# Inputs.net
KiCad netlist of a schematic drawn in Altium Designer
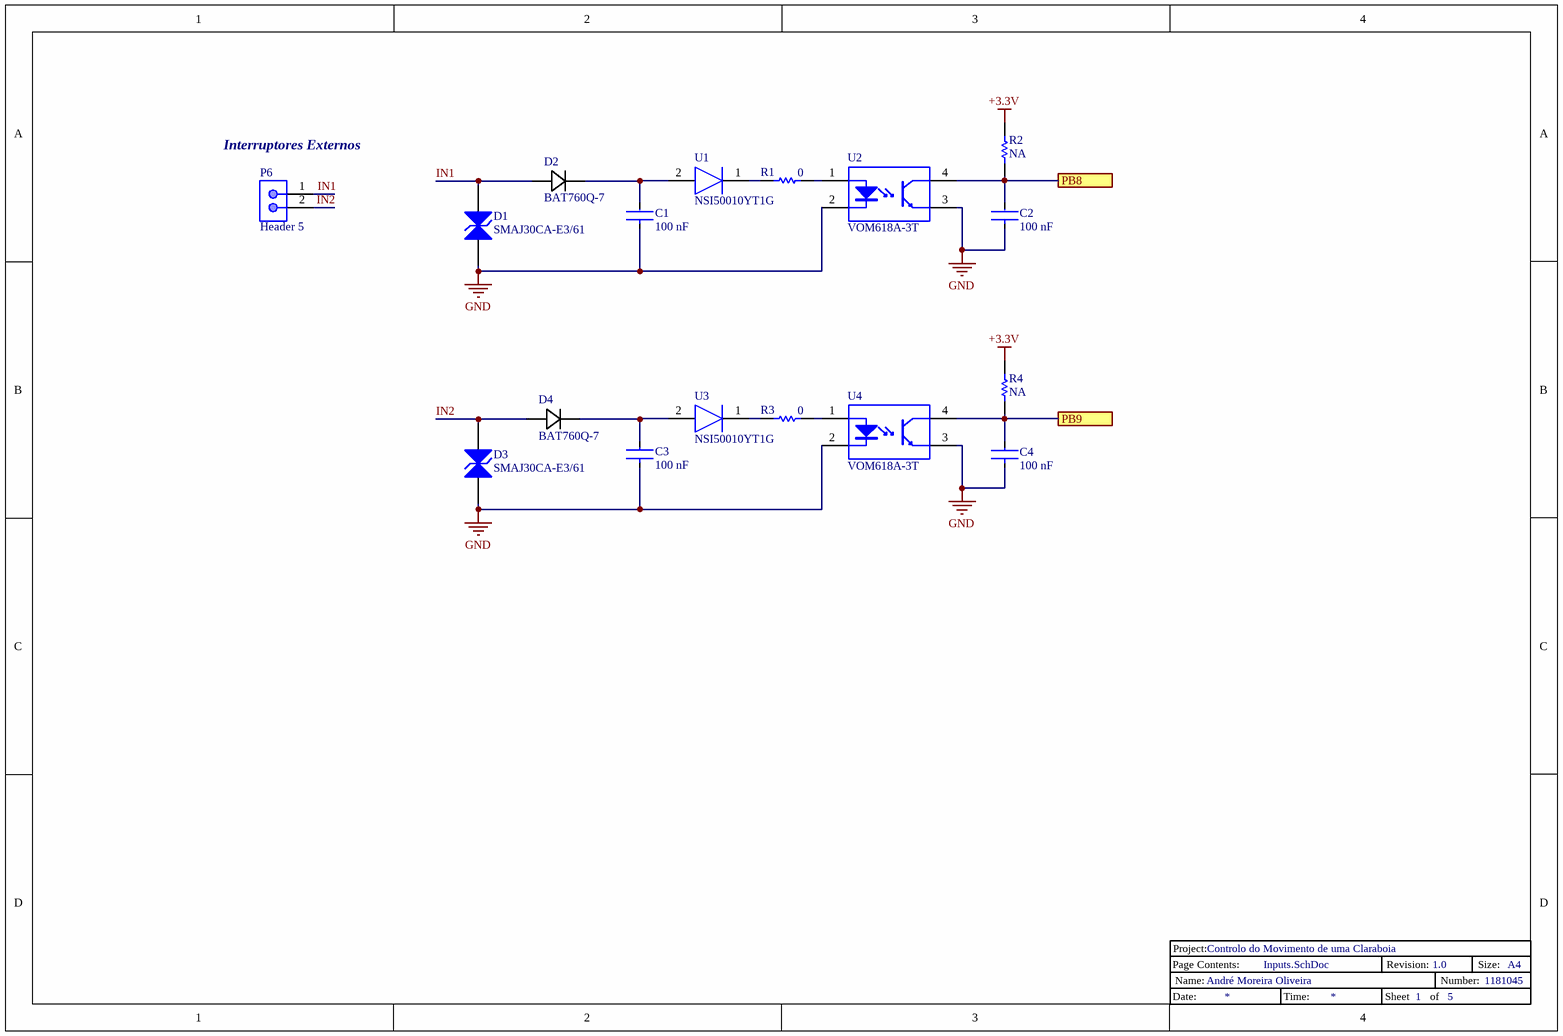
[diagram p0: Inputs.SchDoc]

(export (version "E")
  (design (tool "Eeschema 10.0.6"))
  (components
    (comp (ref "C1")
      (value "100 nF")
      (footprint "FP-CC0603-DA-MFG")
      (description "CAP CER 0.1UF 50V X7R 0603")
      (fields (field (name "MANUFACTURER") "YAGEO") (field (name "VOLTAGE") "50 V"))
      (libsource (lib "Altium Content Vault") (part "11868f565c42a9108669ba33697ecf6"))
    )
    (comp (ref "C2")
      (value "100 nF")
      (footprint "FP-CC0603-DA-MFG")
      (description "CAP CER 0.1UF 50V X7R 0603")
      (fields (field (name "MANUFACTURER") "YAGEO") (field (name "VOLTAGE") "50 V"))
      (libsource (lib "Altium Content Vault") (part "11868f565c42a9108669ba33697ecf6"))
    )
    (comp (ref "C3")
      (value "100 nF")
      (footprint "FP-CC0603-DA-MFG")
      (description "CAP CER 0.1UF 50V X7R 0603")
      (fields (field (name "MANUFACTURER") "YAGEO") (field (name "VOLTAGE") "50 V"))
      (libsource (lib "Altium Content Vault") (part "11868f565c42a9108669ba33697ecf6"))
    )
    (comp (ref "C4")
      (value "100 nF")
      (footprint "FP-CC0603-DA-MFG")
      (description "CAP CER 0.1UF 50V X7R 0603")
      (fields (field (name "MANUFACTURER") "YAGEO") (field (name "VOLTAGE") "50 V"))
      (libsource (lib "Altium Content Vault") (part "11868f565c42a9108669ba33697ecf6"))
    )
    (comp (ref "D1")
      (value "SMAJ30CA-E3/61")
      (footprint "VISH-DO-214AC-2_L")
      (fields (field (name "MANUFACTURER") "Vishay Semiconductor"))
      (libsource (lib "Altium Content Vault") (part "VISH-A1A2-2"))
    )
    (comp (ref "D2")
      (value "BAT760Q-7")
      (footprint "DIODE_SOD-323_1P7X1P3_DIO-L")
      (description "No Description Available")
      (fields (field (name "COPYRIGHT") "Copyright (C) 2018 Accelerated Designs. All rights reserved"))
      (libsource (lib "BAT760Q-7") (part "BAT760Q-7"))
    )
    (comp (ref "D3")
      (value "SMAJ30CA-E3/61")
      (footprint "VISH-DO-214AC-2_L")
      (fields (field (name "MANUFACTURER") "Vishay Semiconductor"))
      (libsource (lib "Altium Content Vault") (part "VISH-A1A2-2"))
    )
    (comp (ref "D4")
      (value "BAT760Q-7")
      (footprint "DIODE_SOD-323_1P7X1P3_DIO-L")
      (description "No Description Available")
      (fields (field (name "COPYRIGHT") "Copyright (C) 2018 Accelerated Designs. All rights reserved"))
      (libsource (lib "BAT760Q-7") (part "BAT760Q-7"))
    )
    (comp (ref "P6")
      (value "Header 5")
      (footprint "MOLX-22-27-2021_V")
      (fields (field (name "MANUFACTURER") "Molex") (field (name "PARTNUMBER") "0022272021"))
      (libsource (lib "Altium Content Vault") (part "CN-1P-M-R2"))
    )
    (comp (ref "R1")
      (value "0")
      (footprint "RESC1608X55X25ML10T15")
      (description "Chip Resistor, 0 Ohm, +/- 5%, 0.1 W, -55 to 155 degC, 0603 (1608 Metric), RoHS, Tape and Reel")
      (fields (field (name "TOLERANCE") "5%") (field (name "MANUFACTURER") "Yageo"))
      (libsource (lib "Altium Content Vault") (part "RES-2"))
    )
    (comp (ref "R2")
      (value "NA")
      (footprint "RESC1608X55X25ML10T15")
      (description "Chip Resistor, 0 Ohm, +/- 5%, 0.1 W, -55 to 155 degC, 0603 (1608 Metric), RoHS, Tape and Reel")
      (fields (field (name "TOLERANCE") "5%") (field (name "MANUFACTURER") "Yageo"))
      (libsource (lib "Altium Content Vault") (part "RES-2"))
    )
    (comp (ref "R3")
      (value "0")
      (footprint "RESC1608X55X25ML10T15")
      (description "Chip Resistor, 0 Ohm, +/- 5%, 0.1 W, -55 to 155 degC, 0603 (1608 Metric), RoHS, Tape and Reel")
      (fields (field (name "TOLERANCE") "5%") (field (name "MANUFACTURER") "Yageo"))
      (libsource (lib "Altium Content Vault") (part "RES-2"))
    )
    (comp (ref "R4")
      (value "NA")
      (footprint "RESC1608X55X25ML10T15")
      (description "Chip Resistor, 0 Ohm, +/- 5%, 0.1 W, -55 to 155 degC, 0603 (1608 Metric), RoHS, Tape and Reel")
      (fields (field (name "TOLERANCE") "5%") (field (name "MANUFACTURER") "Yageo"))
      (libsource (lib "Altium Content Vault") (part "RES-2"))
    )
    (comp (ref "Title_Block_1") (value "Title_Block") (libsource (lib "Title_Block") (part "Title_Block")))
    (comp (ref "U1")
      (value "NSI50010YT1G")
      (footprint "SamacSys:SOD3716X135N")
      (description "Diode")
      (fields (field (name "MOUSER PART NUMBER") "863-NSI50010YT1G"))
      (libsource (lib "*") (part "NSI50010YT1G"))
    )
    (comp (ref "U2")
      (value "VOM618A-3T")
      (footprint "VISH-SOP-4_V")
      (fields (field (name "MANUFACTURER") "Vishay"))
      (libsource (lib "Altium Content Vault") (part "OPTO-AKEC-4"))
    )
    (comp (ref "U3")
      (value "NSI50010YT1G")
      (footprint "SamacSys:SOD3716X135N")
      (description "Diode")
      (fields (field (name "MOUSER PART NUMBER") "863-NSI50010YT1G"))
      (libsource (lib "*") (part "NSI50010YT1G"))
    )
    (comp (ref "U4")
      (value "VOM618A-3T")
      (footprint "VISH-SOP-4_V")
      (fields (field (name "MANUFACTURER") "Vishay"))
      (libsource (lib "Altium Content Vault") (part "OPTO-AKEC-4"))
    )
  )
  (nets
    (net (code "1") (name "+3.3V") (class "Default")
      (node (ref "R2") (pin "2") (pinfunction "2_2") (pintype "passive"))
      (node (ref "R4") (pin "2") (pinfunction "2_2") (pintype "passive"))
    )
    (net (code "2") (name "/IN1") (class "Default")
      (node (ref "D1") (pin "2") (pinfunction "A2_2") (pintype "passive"))
      (node (ref "D2") (pin "2") (pinfunction "2_2") (pintype "passive"))
      (node (ref "P6") (pin "1") (pinfunction "1_1") (pintype "passive"))
    )
    (net (code "3") (name "/IN2") (class "Default")
      (node (ref "D3") (pin "2") (pinfunction "A2_2") (pintype "passive"))
      (node (ref "D4") (pin "2") (pinfunction "2_2") (pintype "passive"))
      (node (ref "P6") (pin "2") (pinfunction "2_2") (pintype "passive"))
    )
    (net (code "4") (name "/PB8") (class "Default")
      (node (ref "C2") (pin "2") (pinfunction "2_2") (pintype "passive"))
      (node (ref "R2") (pin "1") (pinfunction "1_1") (pintype "passive"))
      (node (ref "U2") (pin "4") (pinfunction "COLLECTOR_4") (pintype "passive"))
    )
    (net (code "5") (name "/PB9") (class "Default")
      (node (ref "C4") (pin "2") (pinfunction "2_2") (pintype "passive"))
      (node (ref "R4") (pin "1") (pinfunction "1_1") (pintype "passive"))
      (node (ref "U4") (pin "4") (pinfunction "COLLECTOR_4") (pintype "passive"))
    )
    (net (code "6") (name "GND") (class "Default")
      (node (ref "C1") (pin "1") (pinfunction "1_1") (pintype "passive"))
      (node (ref "C2") (pin "1") (pinfunction "1_1") (pintype "passive"))
      (node (ref "C3") (pin "1") (pinfunction "1_1") (pintype "passive"))
      (node (ref "C4") (pin "1") (pinfunction "1_1") (pintype "passive"))
      (node (ref "D1") (pin "1") (pinfunction "A1_1") (pintype "passive"))
      (node (ref "D3") (pin "1") (pinfunction "A1_1") (pintype "passive"))
      (node (ref "U2") (pin "2") (pinfunction "CATHODE_2") (pintype "passive"))
      (node (ref "U2") (pin "3") (pinfunction "EMITTER_3") (pintype "passive"))
      (node (ref "U4") (pin "2") (pinfunction "CATHODE_2") (pintype "passive"))
      (node (ref "U4") (pin "3") (pinfunction "EMITTER_3") (pintype "passive"))
    )
    (net (code "7") (name "Net-(U1-A)") (class "Default")
      (node (ref "C1") (pin "2") (pinfunction "2_2") (pintype "passive"))
      (node (ref "D2") (pin "1") (pinfunction "1_1") (pintype "passive"))
      (node (ref "U1") (pin "2") (pinfunction "A_2") (pintype "passive"))
    )
    (net (code "8") (name "Net-(U1-K)") (class "Default")
      (node (ref "R1") (pin "1") (pinfunction "1_1") (pintype "passive"))
      (node (ref "U1") (pin "1") (pinfunction "K_1") (pintype "passive"))
    )
    (net (code "9") (name "Net-(U2-ANODE)") (class "Default")
      (node (ref "R1") (pin "2") (pinfunction "2_2") (pintype "passive"))
      (node (ref "U2") (pin "1") (pinfunction "ANODE_1") (pintype "passive"))
    )
    (net (code "10") (name "Net-(U3-A)") (class "Default")
      (node (ref "C3") (pin "2") (pinfunction "2_2") (pintype "passive"))
      (node (ref "D4") (pin "1") (pinfunction "1_1") (pintype "passive"))
      (node (ref "U3") (pin "2") (pinfunction "A_2") (pintype "passive"))
    )
    (net (code "11") (name "Net-(U3-K)") (class "Default")
      (node (ref "R3") (pin "1") (pinfunction "1_1") (pintype "passive"))
      (node (ref "U3") (pin "1") (pinfunction "K_1") (pintype "passive"))
    )
    (net (code "12") (name "Net-(U4-ANODE)") (class "Default")
      (node (ref "R3") (pin "2") (pinfunction "2_2") (pintype "passive"))
      (node (ref "U4") (pin "1") (pinfunction "ANODE_1") (pintype "passive"))
    )
  )
)
